# llg_schematic.net
KiCad netlist of a schematic drawn in EAGLE
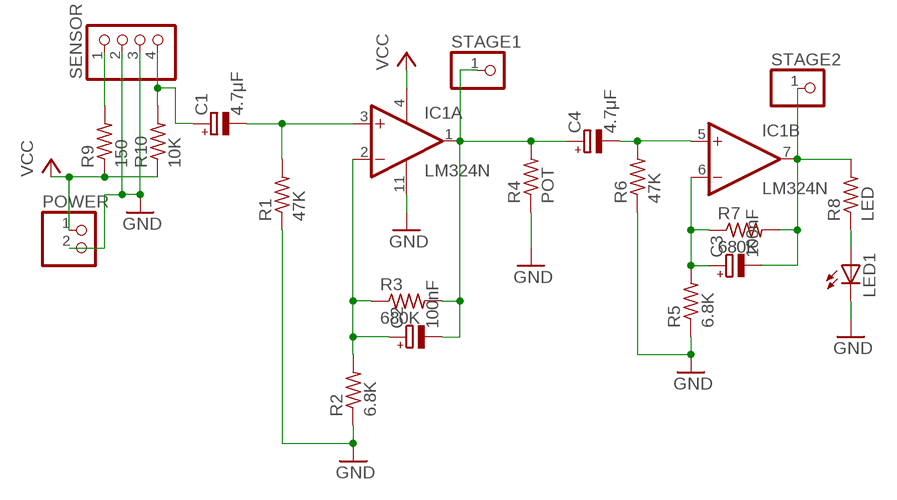
[diagram p0: schematic, sheet 1]

(export (version "E")
  (design (tool "Eeschema 10.0.6"))
  (components
    (comp (ref "C1")
      (value "4.7μF")
      (footprint "eagle-import:E2,5-6")
      (libsource (lib "eagle-import") (part "CPOL-EUE2.5-6"))
    )
    (comp (ref "C2")
      (value "100nF")
      (footprint "eagle-import:E2,5-6")
      (libsource (lib "eagle-import") (part "CPOL-EUE2.5-6"))
    )
    (comp (ref "C3")
      (value "100nF")
      (footprint "eagle-import:E2,5-6")
      (libsource (lib "eagle-import") (part "CPOL-EUE2.5-6"))
    )
    (comp (ref "C4")
      (value "4.7μF")
      (footprint "eagle-import:E2,5-6")
      (libsource (lib "eagle-import") (part "CPOL-EUE2.5-6"))
    )
    (comp (ref "IC1")
      (value "LM324N")
      (footprint "eagle-import:DIL14")
      (libsource (lib "eagle-import") (part "LM324N"))
    )
    (comp (ref "LED1")
      (value "LED5MM")
      (footprint "eagle-import:LED5MM")
      (libsource (lib "eagle-import") (part "LED5MM"))
    )
    (comp (ref "POWER")
      (value "PINHD-1X2")
      (footprint "eagle-import:1X02")
      (libsource (lib "eagle-import") (part "PINHD-1X2"))
    )
    (comp (ref "R1")
      (value "47K")
      (footprint "eagle-import:0204_7")
      (libsource (lib "eagle-import") (part "R-US_0204/7"))
    )
    (comp (ref "R2")
      (value "6.8K")
      (footprint "eagle-import:0204_7")
      (libsource (lib "eagle-import") (part "R-US_0204/7"))
    )
    (comp (ref "R3")
      (value "680K")
      (footprint "eagle-import:0204_7")
      (libsource (lib "eagle-import") (part "R-US_0204/7"))
    )
    (comp (ref "R4")
      (value "POT")
      (footprint "eagle-import:0204_7")
      (libsource (lib "eagle-import") (part "R-US_0204/7"))
    )
    (comp (ref "R5")
      (value "6.8K")
      (footprint "eagle-import:0204_7")
      (libsource (lib "eagle-import") (part "R-US_0204/7"))
    )
    (comp (ref "R6")
      (value "47K")
      (footprint "eagle-import:0204_7")
      (libsource (lib "eagle-import") (part "R-US_0204/7"))
    )
    (comp (ref "R7")
      (value "680K")
      (footprint "eagle-import:0204_7")
      (libsource (lib "eagle-import") (part "R-US_0204/7"))
    )
    (comp (ref "R8")
      (value "LED")
      (footprint "eagle-import:0204_7")
      (libsource (lib "eagle-import") (part "R-US_0204/7"))
    )
    (comp (ref "R9")
      (value "150")
      (footprint "eagle-import:0204_7")
      (libsource (lib "eagle-import") (part "R-US_0204/7"))
    )
    (comp (ref "R10")
      (value "10K")
      (footprint "eagle-import:0204_7")
      (libsource (lib "eagle-import") (part "R-US_0204/7"))
    )
    (comp (ref "SENSOR")
      (value "PINHD-1X4")
      (footprint "eagle-import:1X04")
      (libsource (lib "eagle-import") (part "PINHD-1X4"))
    )
    (comp (ref "STAGE1")
      (value "PINHD-1X1")
      (footprint "eagle-import:1X01")
      (libsource (lib "eagle-import") (part "PINHD-1X1"))
    )
    (comp (ref "STAGE2")
      (value "PINHD-1X1")
      (footprint "eagle-import:1X01")
      (libsource (lib "eagle-import") (part "PINHD-1X1"))
    )
  )
  (nets
    (net (code "1") (name "GND") (class "Default")
      (node (ref "IC1") (pin "11") (pinfunction "V-_11") (pintype "power_in"))
      (node (ref "LED1") (pin "K") (pinfunction "C_K") (pintype "passive"))
      (node (ref "POWER") (pin "2") (pinfunction "2_2") (pintype "passive"))
      (node (ref "R1") (pin "1") (pinfunction "1_1") (pintype "passive"))
      (node (ref "R2") (pin "1") (pinfunction "1_1") (pintype "passive"))
      (node (ref "R4") (pin "1") (pinfunction "1_1") (pintype "passive"))
      (node (ref "R5") (pin "1") (pinfunction "1_1") (pintype "passive"))
      (node (ref "R6") (pin "1") (pinfunction "1_1") (pintype "passive"))
      (node (ref "SENSOR") (pin "2") (pinfunction "2_2") (pintype "passive"))
      (node (ref "SENSOR") (pin "3") (pinfunction "3_3") (pintype "passive"))
    )
    (net (code "2") (name "Net-(C1-Pad+)") (class "Default")
      (node (ref "C1") (pin "+") (pinfunction "+_+") (pintype "passive"))
      (node (ref "R10") (pin "2") (pinfunction "2_2") (pintype "passive"))
      (node (ref "SENSOR") (pin "4") (pinfunction "4_4") (pintype "passive"))
    )
    (net (code "3") (name "Net-(IC1A-+IN)") (class "Default")
      (node (ref "C1") (pin "-") (pinfunction "-_-") (pintype "passive"))
      (node (ref "IC1") (pin "3") (pinfunction "+IN_3") (pintype "input"))
      (node (ref "R1") (pin "2") (pinfunction "2_2") (pintype "passive"))
    )
    (net (code "4") (name "Net-(IC1A--IN)") (class "Default")
      (node (ref "C2") (pin "+") (pinfunction "+_+") (pintype "passive"))
      (node (ref "IC1") (pin "2") (pinfunction "-IN_2") (pintype "input"))
      (node (ref "R2") (pin "2") (pinfunction "2_2") (pintype "passive"))
      (node (ref "R3") (pin "1") (pinfunction "1_1") (pintype "passive"))
    )
    (net (code "5") (name "Net-(IC1A-OUT)") (class "Default")
      (node (ref "C2") (pin "-") (pinfunction "-_-") (pintype "passive"))
      (node (ref "C4") (pin "+") (pinfunction "+_+") (pintype "passive"))
      (node (ref "IC1") (pin "1") (pinfunction "OUT_1") (pintype "output"))
      (node (ref "R3") (pin "2") (pinfunction "2_2") (pintype "passive"))
      (node (ref "R4") (pin "2") (pinfunction "2_2") (pintype "passive"))
      (node (ref "STAGE1") (pin "1") (pinfunction "1_1") (pintype "passive"))
    )
    (net (code "6") (name "Net-(IC1B-+IN)") (class "Default")
      (node (ref "C4") (pin "-") (pinfunction "-_-") (pintype "passive"))
      (node (ref "IC1") (pin "5") (pinfunction "+IN_5") (pintype "input"))
      (node (ref "R6") (pin "2") (pinfunction "2_2") (pintype "passive"))
    )
    (net (code "7") (name "Net-(IC1B--IN)") (class "Default")
      (node (ref "C3") (pin "+") (pinfunction "+_+") (pintype "passive"))
      (node (ref "IC1") (pin "6") (pinfunction "-IN_6") (pintype "input"))
      (node (ref "R5") (pin "2") (pinfunction "2_2") (pintype "passive"))
      (node (ref "R7") (pin "1") (pinfunction "1_1") (pintype "passive"))
    )
    (net (code "8") (name "Net-(IC1B-OUT)") (class "Default")
      (node (ref "C3") (pin "-") (pinfunction "-_-") (pintype "passive"))
      (node (ref "IC1") (pin "7") (pinfunction "OUT_7") (pintype "output"))
      (node (ref "R7") (pin "2") (pinfunction "2_2") (pintype "passive"))
      (node (ref "R8") (pin "2") (pinfunction "2_2") (pintype "passive"))
      (node (ref "STAGE2") (pin "1") (pinfunction "1_1") (pintype "passive"))
    )
    (net (code "9") (name "Net-(LED1-PadA)") (class "Default")
      (node (ref "LED1") (pin "A") (pinfunction "A_A") (pintype "passive"))
      (node (ref "R8") (pin "1") (pinfunction "1_1") (pintype "passive"))
    )
    (net (code "10") (name "Net-(R9-Pad2)") (class "Default")
      (node (ref "R9") (pin "2") (pinfunction "2_2") (pintype "passive"))
      (node (ref "SENSOR") (pin "1") (pinfunction "1_1") (pintype "passive"))
    )
    (net (code "11") (name "VCC") (class "Default")
      (node (ref "IC1") (pin "4") (pinfunction "V+_4") (pintype "power_in"))
      (node (ref "POWER") (pin "1") (pinfunction "1_1") (pintype "passive"))
      (node (ref "R10") (pin "1") (pinfunction "1_1") (pintype "passive"))
      (node (ref "R9") (pin "1") (pinfunction "1_1") (pintype "passive"))
    )
  )
)
